# controller.net
KiCad netlist of a schematic drawn in Altium Designer
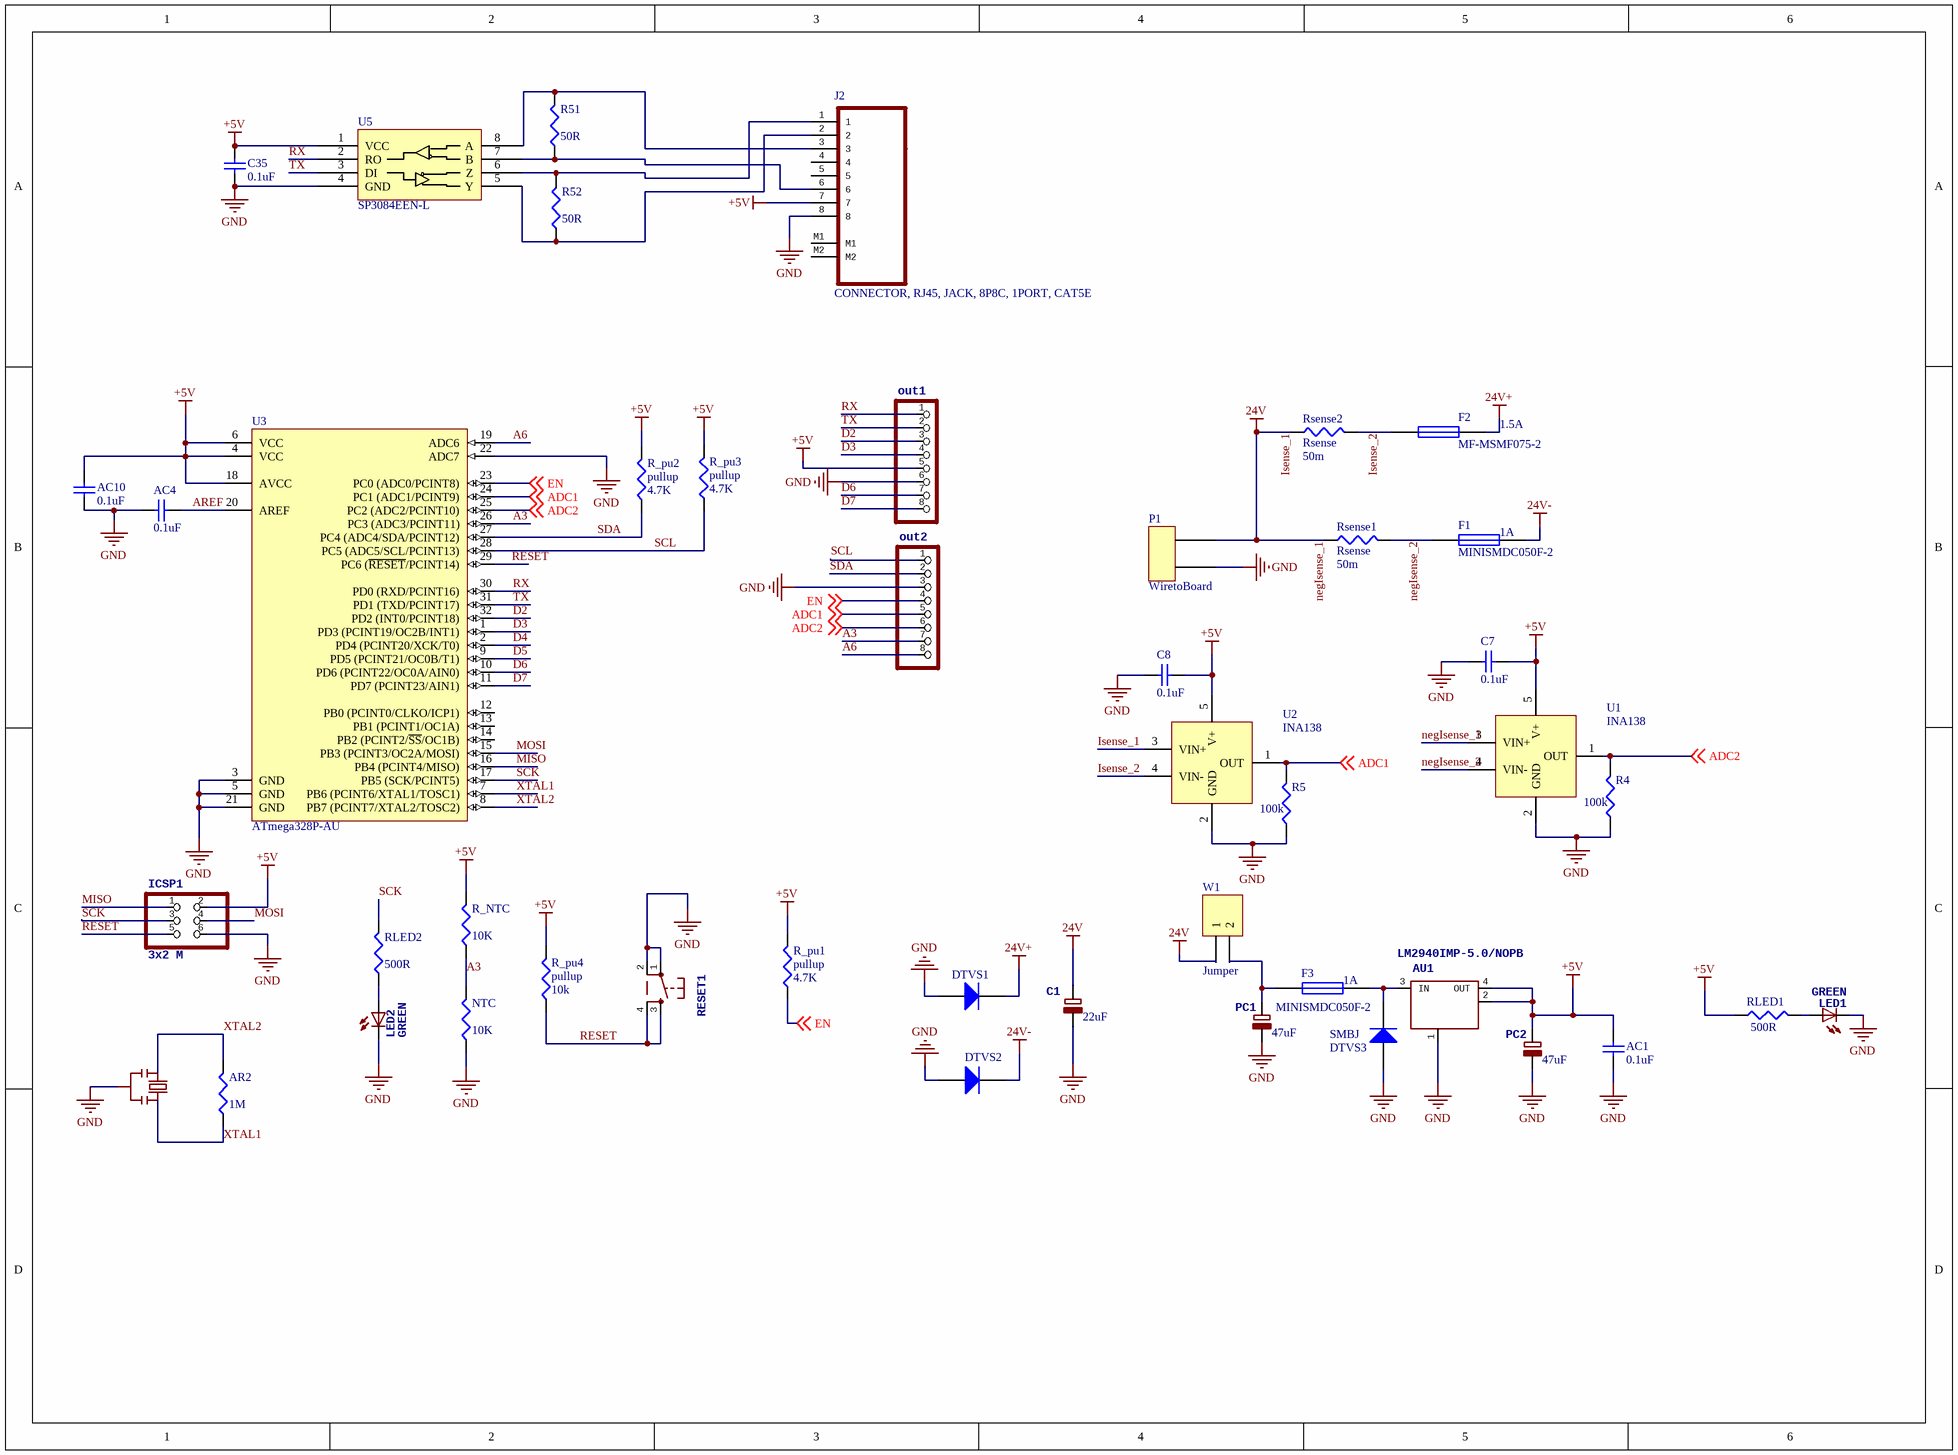
[diagram p0: controller.SchDoc]

(export (version "E")
  (design (tool "Eeschema 10.0.6"))
  (components
    (comp (ref "AC1")
      (value "0.1uF")
      (footprint "1608[0603]")
      (description "Capacitor (Semiconductor SIM Model)")
      (fields
        (field (name "PARTNO") "CC0603KRX7R9BB104")
        (field (name "Comment") "100n")
        (field (name "PUBLISHER") "Altium Limited")
      )
      (libsource (lib "Miscellaneous Devices") (part "Cap Semi"))
    )
    (comp (ref "AC4")
      (value "0.1uF")
      (footprint "1608[0603]")
      (description "Capacitor (Semiconductor SIM Model)")
      (fields
        (field (name "PARTNO") "CC0603KRX7R9BB104")
        (field (name "Comment") "Cap Semi")
        (field (name "PUBLISHER") "Altium Limited")
      )
      (libsource (lib "Miscellaneous Devices") (part "Cap Semi"))
    )
    (comp (ref "AC10")
      (value "0.1uF")
      (footprint "1608[0603]")
      (description "Capacitor (Semiconductor SIM Model)")
      (fields
        (field (name "PARTNO") "CC0603KRX7R9BB104")
        (field (name "Comment") "Cap Semi")
        (field (name "PUBLISHER") "Altium Limited")
      )
      (libsource (lib "Miscellaneous Devices") (part "Cap Semi"))
    )
    (comp (ref "AR2")
      (value "1M")
      (footprint "J1-0603")
      (description "Resistor")
      (fields (field (name "PUBLISHER") "Altium Limited"))
      (libsource (lib "Miscellaneous Devices") (part "Res3"))
    )
    (comp (ref "AU1")
      (value "LM2940IMP-5.0/NOPB")
      (footprint "SOT223")
      (description "1469076")
      (libsource (lib "arduino_Uno_Rev3-02-TH") (part "MC33269ST*"))
    )
    (comp (ref "C1")
      (value "22uF")
      (footprint "PANASONIC_D")
      (fields (field (name "PARTNO") "EMZA500ADA220MF61G"))
      (libsource (lib "G2_LV") (part "CPOL-EUD"))
    )
    (comp (ref "C7")
      (value "0.1uF")
      (footprint "1608[0603]")
      (description "Capacitor (Semiconductor SIM Model)")
      (fields
        (field (name "PARTNO") "CC0603KRX7R9BB104")
        (field (name "Comment") "Cap Semi")
        (field (name "PUBLISHER") "Altium Limited")
      )
      (libsource (lib "Miscellaneous Devices") (part "Cap Semi"))
    )
    (comp (ref "C8")
      (value "0.1uF")
      (footprint "1608[0603]")
      (description "Capacitor (Semiconductor SIM Model)")
      (fields
        (field (name "PARTNO") "CC0603KRX7R9BB104")
        (field (name "Comment") "Cap Semi")
        (field (name "PUBLISHER") "Altium Limited")
      )
      (libsource (lib "Miscellaneous Devices") (part "Cap Semi"))
    )
    (comp (ref "C35")
      (value "0.1uF")
      (footprint "1608[0603]")
      (description "Capacitor (Semiconductor SIM Model)")
      (fields
        (field (name "PARTNO") "CC0603KRX7R9BB104")
        (field (name "Comment") "Cap Semi")
        (field (name "PUBLISHER") "Altium Limited")
      )
      (libsource (lib "Miscellaneous Devices") (part "Cap Semi"))
    )
    (comp (ref "DTVS1")
      (value "SMBJ24A-E3/52")
      (footprint "DO-214AA")
      (description "TVS")
      (fields (field (name "PUBLISHER") "Altium Limited"))
      (libsource (lib "G2_LV") (part "SMBJ"))
    )
    (comp (ref "DTVS2")
      (value "SMBJ")
      (footprint "DO-214AA")
      (description "TVS")
      (fields (field (name "PARTNO") "SMBJ24A-E3/52") (field (name "PUBLISHER") "Altium Limited"))
      (libsource (lib "G2_LV") (part "SMBJ"))
    )
    (comp (ref "DTVS3")
      (value "SMBJ")
      (footprint "DO-214AA")
      (description "TVS")
      (fields (field (name "PARTNO") "SMBJ24A-E3/52") (field (name "PUBLISHER") "Altium Limited"))
      (libsource (lib "G2_LV") (part "SMBJ"))
    )
    (comp (ref "F1")
      (value "MINISMDC050F-2")
      (footprint "MF-MSMF1")
      (description "Fuse")
      (fields (field (name "TRIPPING CURRENT") "1A") (field (name "PUBLISHER") "Altium Limited"))
      (libsource (lib "G2_LV") (part "Fuse 1"))
    )
    (comp (ref "F2")
      (value "MF-MSMF075-2")
      (footprint "MF-MSMF1")
      (description "Fuse")
      (fields
        (field (name "TRIPPING CURRENT") "1.5A")
        (field (name "PARTNO") "MF-MSMF075/24-2")
        (field (name "PUBLISHER") "Altium Limited")
      )
      (libsource (lib "G2_LV") (part "Fuse 1"))
    )
    (comp (ref "F3")
      (value "MINISMDC050F-2")
      (footprint "MF-MSMF1")
      (description "Fuse")
      (fields (field (name "TRIPPING CURRENT") "1A") (field (name "PUBLISHER") "Altium Limited"))
      (libsource (lib "G2_LV") (part "Fuse 1"))
    )
    (comp (ref "ICSP1")
      (value "3x2 M")
      (footprint "2X03")
      (fields (field (name "PARTNO") "M20-9980345"))
      (libsource (lib "SmartPrj") (part "PINHD-2X3"))
    )
    (comp (ref "J2")
      (value "CONNECTOR, RJ45, JACK, 8P8C, 1PORT, CAT5E")
      (footprint "MOLEX_85505-5113")
      (fields (field (name "MPN") "85505-5113"))
      (libsource (lib "G2_LV") (part "85505-5113"))
    )
    (comp (ref "LED1")
      (value "GREEN")
      (footprint "CHIP-LED0805")
      (fields (field (name "PARTNO") "KPT-2012SGC"))
      (libsource (lib "led") (part "LEDCHIP-LED0805"))
    )
    (comp (ref "LED2")
      (value "GREEN")
      (footprint "CHIP-LED0805")
      (fields (field (name "PARTNO") "KPT-2012SGC"))
      (libsource (lib "led") (part "LEDCHIP-LED0805"))
    )
    (comp (ref "NTC")
      (value "10K")
      (footprint "J1-0603")
      (description "Resistor")
      (fields (field (name "PARTNO") "NCP18XH103J03RB") (field (name "PUBLISHER") "Altium Limited"))
      (libsource (lib "Miscellaneous Devices") (part "Res3"))
    )
    (comp (ref "out1")
      (value "~")
      (footprint "1X08")
      (fields (field (name "PARTNO") "5-534237-4"))
      (libsource (lib "SmartPrj") (part "PINHD-1X8"))
    )
    (comp (ref "out2")
      (value "~")
      (footprint "1X08")
      (fields (field (name "PARTNO") "5-534237-4"))
      (libsource (lib "SmartPrj") (part "PINHD-1X8"))
    )
    (comp (ref "P1")
      (value "WiretoBoard")
      (footprint "MC000044")
      (fields (field (name "PARTNO") "64T3402"))
      (libsource (lib "PCB_Project") (part "WiretoBoard"))
    )
    (comp (ref "PC1")
      (value "47uF")
      (footprint "PANASONIC_D")
      (fields
        (field (name "PARTNO") "EEE1EA470WAP")
        (field (name "Comment") "<B>POLARIZED CAPACITOR</B>, European symbol")
      )
      (libsource (lib "G2_LV") (part "CPOL-EUD"))
    )
    (comp (ref "PC2")
      (value "47uF")
      (footprint "PANASONIC_D")
      (fields
        (field (name "PARTNO") "EEE1EA470WAP")
        (field (name "Comment") "<B>POLARIZED CAPACITOR</B>, European symbol")
      )
      (libsource (lib "G2_LV") (part "CPOL-EUD"))
    )
    (comp (ref "R4")
      (value "100k")
      (footprint "J1-0603")
      (description "Resistor")
      (fields (field (name "Comment") "Res3") (field (name "PUBLISHER") "Altium Limited"))
      (libsource (lib "Miscellaneous Devices") (part "Res3"))
    )
    (comp (ref "R5")
      (value "100k")
      (footprint "J1-0603")
      (description "Resistor")
      (fields (field (name "Comment") "Res3") (field (name "PUBLISHER") "Altium Limited"))
      (libsource (lib "Miscellaneous Devices") (part "Res3"))
    )
    (comp (ref "R51")
      (value "50R")
      (footprint "J1-0603")
      (description "Resistor")
      (fields (field (name "PUBLISHER") "Altium Limited"))
      (libsource (lib "Miscellaneous Devices") (part "Res3"))
    )
    (comp (ref "R52")
      (value "50R")
      (footprint "J1-0603")
      (description "Resistor")
      (fields (field (name "PUBLISHER") "Altium Limited"))
      (libsource (lib "Miscellaneous Devices") (part "Res3"))
    )
    (comp (ref "RESET1")
      (value "~")
      (footprint "B3S-1002")
      (fields (field (name "PARTNO") "B3S-1002"))
      (libsource (lib "arduino_Uno_Rev3-02-TH") (part "TS42"))
    )
    (comp (ref "RLED1")
      (value "500R")
      (footprint "J1-0603")
      (description "Resistor")
      (fields (field (name "PUBLISHER") "Altium Limited"))
      (libsource (lib "Miscellaneous Devices") (part "Res3"))
    )
    (comp (ref "RLED2")
      (value "500R")
      (footprint "J1-0603")
      (description "Resistor")
      (fields (field (name "PUBLISHER") "Altium Limited"))
      (libsource (lib "Miscellaneous Devices") (part "Res3"))
    )
    (comp (ref "Rsense1")
      (value "Rsense")
      (footprint "R6432")
      (description "CRF2512-FV-R001ELF")
      (fields
        (field (name "ALTIUM_VALUE") "50m")
        (field (name "PARTNO") "MCS3264R050FER")
        (field (name "PUBLISHER") "Altium Limited")
      )
      (libsource (lib "G2_LV") (part "Rsense"))
    )
    (comp (ref "Rsense2")
      (value "Rsense")
      (footprint "R6432")
      (description "CRF2512-FV-R001ELF")
      (fields
        (field (name "ALTIUM_VALUE") "50m")
        (field (name "PARTNO") "MCS3264R050FER")
        (field (name "PUBLISHER") "Altium Limited")
      )
      (libsource (lib "G2_LV") (part "Rsense"))
    )
    (comp (ref "R_NTC")
      (value "10K")
      (footprint "J1-0603")
      (description "Resistor")
      (fields (field (name "PUBLISHER") "Altium Limited"))
      (libsource (lib "Miscellaneous Devices") (part "Res3"))
    )
    (comp (ref "R_pu1")
      (value "pullup")
      (footprint "J1-0603")
      (description "Resistor")
      (fields (field (name "ALTIUM_VALUE") "4.7K") (field (name "PUBLISHER") "Altium Limited"))
      (libsource (lib "Miscellaneous Devices") (part "Res3"))
    )
    (comp (ref "R_pu2")
      (value "pullup")
      (footprint "J1-0603")
      (description "Resistor")
      (fields (field (name "ALTIUM_VALUE") "4.7K") (field (name "PUBLISHER") "Altium Limited"))
      (libsource (lib "Miscellaneous Devices") (part "Res3"))
    )
    (comp (ref "R_pu3")
      (value "pullup")
      (footprint "J1-0603")
      (description "Resistor")
      (fields (field (name "ALTIUM_VALUE") "4.7K") (field (name "PUBLISHER") "Altium Limited"))
      (libsource (lib "Miscellaneous Devices") (part "Res3"))
    )
    (comp (ref "R_pu4")
      (value "pullup")
      (footprint "J1-0603")
      (description "Resistor")
      (fields (field (name "ALTIUM_VALUE") "10k") (field (name "PUBLISHER") "Altium Limited"))
      (libsource (lib "Miscellaneous Devices") (part "Res3"))
    )
    (comp (ref "U1")
      (value "INA138")
      (footprint "SOT-23")
      (fields (field (name "PARTNO") "INA138NA/250"))
      (libsource (lib "PCB_Project") (part "INA138"))
    )
    (comp (ref "U2")
      (value "INA138")
      (footprint "SOT-23")
      (fields (field (name "PARTNO") "INA138NA/250"))
      (libsource (lib "PCB_Project") (part "INA138"))
    )
    (comp (ref "U3")
      (value "ATmega328P-AU")
      (footprint "32A_N")
      (libsource (lib "Atmel Microcontroller megaAVR") (part "ATmega328P-AU"))
    )
    (comp (ref "U5")
      (value "SP3084EEN-L")
      (footprint "SOICN8")
      (libsource (lib "G2_LV") (part "SP3084EEN-L"))
    )
    (comp (ref "W1")
      (value "Jumper")
      (footprint "HDR1X2")
      (description "Header, 2-Pin")
      (fields (field (name "PUBLISHER") "Altium Limited"))
      (libsource (lib "Miscellaneous Connectors") (part "Header 2"))
    )
    (comp (ref "Y1")
      (value "~")
      (footprint "RESONATOR")
      (fields (field (name "PARTNO") "CSTCE16M0V53-R0"))
      (libsource (lib "SmartPrj") (part "RESONATORMU"))
    )
  )
  (nets
    (net (code "1") (name "+5V") (class "Default")
      (node (ref "AC1") (pin "2") (pinfunction "2_2") (pintype "passive"))
      (node (ref "AC10") (pin "2") (pinfunction "2_2") (pintype "passive"))
      (node (ref "AU1") (pin "2") (pinfunction "OUT_2") (pintype "passive"))
      (node (ref "AU1") (pin "4") (pinfunction "OUT_4") (pintype "passive"))
      (node (ref "C35") (pin "2") (pinfunction "2_2") (pintype "passive"))
      (node (ref "C7") (pin "2") (pinfunction "2_2") (pintype "passive"))
      (node (ref "C8") (pin "2") (pinfunction "2_2") (pintype "passive"))
      (node (ref "ICSP1") (pin "2") (pinfunction "2_2") (pintype "passive"))
      (node (ref "J2") (pin "7") (pinfunction "7_7") (pintype "passive"))
      (node (ref "PC2") (pin "1") (pinfunction "1_1") (pintype "passive"))
      (node (ref "RLED1") (pin "1") (pinfunction "1_1") (pintype "passive"))
      (node (ref "R_NTC") (pin "2") (pinfunction "2_2") (pintype "passive"))
      (node (ref "R_pu1") (pin "2") (pinfunction "2_2") (pintype "passive"))
      (node (ref "R_pu2") (pin "2") (pinfunction "2_2") (pintype "passive"))
      (node (ref "R_pu3") (pin "2") (pinfunction "2_2") (pintype "passive"))
      (node (ref "R_pu4") (pin "2") (pinfunction "2_2") (pintype "passive"))
      (node (ref "U1") (pin "5") (pinfunction "V+_5") (pintype "passive"))
      (node (ref "U2") (pin "5") (pinfunction "V+_5") (pintype "passive"))
      (node (ref "U3") (pin "18") (pinfunction "AVCC_18") (pintype "power_in"))
      (node (ref "U3") (pin "4") (pinfunction "VCC_4") (pintype "power_in"))
      (node (ref "U3") (pin "6") (pinfunction "VCC_6") (pintype "power_in"))
      (node (ref "U5") (pin "1") (pinfunction "VCC_1") (pintype "passive"))
      (node (ref "out1") (pin "5") (pinfunction "5_5") (pintype "passive"))
    )
    (net (code "2") (name "/A3") (class "Default")
      (node (ref "NTC") (pin "2") (pinfunction "2_2") (pintype "passive"))
      (node (ref "R_NTC") (pin "1") (pinfunction "1_1") (pintype "passive"))
      (node (ref "U3") (pin "26") (pinfunction "PC3_(ADC3/PCINT11)_26") (pintype "bidirectional"))
      (node (ref "out2") (pin "7") (pinfunction "7_7") (pintype "passive"))
    )
    (net (code "3") (name "/A6") (class "Default")
      (node (ref "U3") (pin "19") (pinfunction "ADC6_19") (pintype "input"))
      (node (ref "out2") (pin "8") (pinfunction "8_8") (pintype "passive"))
    )
    (net (code "4") (name "/AREF") (class "Default")
      (node (ref "AC4") (pin "2") (pinfunction "2_2") (pintype "passive"))
      (node (ref "U3") (pin "20") (pinfunction "AREF_20") (pintype "passive"))
    )
    (net (code "5") (name "/D2") (class "Default")
      (node (ref "U3") (pin "32") (pinfunction "PD2_(INT0/PCINT18)_32") (pintype "bidirectional"))
      (node (ref "out1") (pin "3") (pinfunction "3_3") (pintype "passive"))
    )
    (net (code "6") (name "/D3") (class "Default")
      (node (ref "U3") (pin "1") (pinfunction "PD3_(PCINT19/OC2B/INT1)_1") (pintype "bidirectional"))
      (node (ref "out1") (pin "4") (pinfunction "4_4") (pintype "passive"))
    )
    (net (code "7") (name "/D4") (class "Default")
      (node (ref "U3") (pin "2") (pinfunction "PD4_(PCINT20/XCK/T0)_2") (pintype "bidirectional"))
    )
    (net (code "8") (name "/D5") (class "Default")
      (node (ref "U3") (pin "9") (pinfunction "PD5_(PCINT21/OC0B/T1)_9") (pintype "bidirectional"))
    )
    (net (code "9") (name "/D6") (class "Default")
      (node (ref "U3") (pin "10") (pinfunction "PD6_(PCINT22/OC0A/AIN0)_10") (pintype "bidirectional"))
      (node (ref "out1") (pin "7") (pinfunction "7_7") (pintype "passive"))
    )
    (net (code "10") (name "/D7") (class "Default")
      (node (ref "U3") (pin "11") (pinfunction "PD7_(PCINT23/AIN1)_11") (pintype "bidirectional"))
      (node (ref "out1") (pin "8") (pinfunction "8_8") (pintype "passive"))
    )
    (net (code "11") (name "/Isense_2") (class "Default")
      (node (ref "F2") (pin "1") (pinfunction "1_1") (pintype "passive"))
      (node (ref "Rsense2") (pin "2") (pinfunction "2_2") (pintype "passive"))
      (node (ref "U2") (pin "4") (pinfunction "VIN-_4") (pintype "passive"))
    )
    (net (code "12") (name "/MISO") (class "Default")
      (node (ref "ICSP1") (pin "1") (pinfunction "1_1") (pintype "passive"))
      (node (ref "U3") (pin "16") (pinfunction "PB4_(PCINT4/MISO)_16") (pintype "bidirectional"))
    )
    (net (code "13") (name "/MOSI") (class "Default")
      (node (ref "ICSP1") (pin "4") (pinfunction "4_4") (pintype "passive"))
      (node (ref "U3") (pin "15") (pinfunction "PB3_(PCINT3/OC2A/MOSI)_15") (pintype "bidirectional"))
    )
    (net (code "14") (name "/RESET") (class "Default")
      (node (ref "ICSP1") (pin "5") (pinfunction "5_5") (pintype "passive"))
      (node (ref "RESET1") (pin "3") (pinfunction "3_3") (pintype "passive"))
      (node (ref "RESET1") (pin "4") (pinfunction "4_4") (pintype "passive"))
      (node (ref "R_pu4") (pin "1") (pinfunction "1_1") (pintype "passive"))
      (node (ref "U3") (pin "29") (pinfunction "PC6_(~{RESET}/PCINT14)_29") (pintype "bidirectional"))
    )
    (net (code "15") (name "/RX") (class "Default")
      (node (ref "U3") (pin "30") (pinfunction "PD0_(RXD/PCINT16)_30") (pintype "bidirectional"))
      (node (ref "U5") (pin "2") (pinfunction "RO_2") (pintype "passive"))
      (node (ref "out1") (pin "1") (pinfunction "1_1") (pintype "passive"))
    )
    (net (code "16") (name "/SCK") (class "Default")
      (node (ref "ICSP1") (pin "3") (pinfunction "3_3") (pintype "passive"))
      (node (ref "RLED2") (pin "2") (pinfunction "2_2") (pintype "passive"))
      (node (ref "U3") (pin "17") (pinfunction "PB5_(SCK/PCINT5)_17") (pintype "bidirectional"))
    )
    (net (code "17") (name "/SCL") (class "Default")
      (node (ref "R_pu3") (pin "1") (pinfunction "1_1") (pintype "passive"))
      (node (ref "U3") (pin "28") (pinfunction "PC5_(ADC5/SCL/PCINT13)_28") (pintype "bidirectional"))
      (node (ref "out2") (pin "1") (pinfunction "1_1") (pintype "passive"))
    )
    (net (code "18") (name "/SDA") (class "Default")
      (node (ref "R_pu2") (pin "1") (pinfunction "1_1") (pintype "passive"))
      (node (ref "U3") (pin "27") (pinfunction "PC4_(ADC4/SDA/PCINT12)_27") (pintype "bidirectional"))
      (node (ref "out2") (pin "2") (pinfunction "2_2") (pintype "passive"))
    )
    (net (code "19") (name "/TX") (class "Default")
      (node (ref "U3") (pin "31") (pinfunction "PD1_(TXD/PCINT17)_31") (pintype "bidirectional"))
      (node (ref "U5") (pin "3") (pinfunction "DI_3") (pintype "passive"))
      (node (ref "out1") (pin "2") (pinfunction "2_2") (pintype "passive"))
    )
    (net (code "20") (name "/XTAL1") (class "Default")
      (node (ref "AR2") (pin "1") (pinfunction "1_1") (pintype "passive"))
      (node (ref "U3") (pin "7") (pinfunction "PB6_(PCINT6/XTAL1/TOSC1)_7") (pintype "bidirectional"))
      (node (ref "Y1") (pin "3") (pinfunction "3_3") (pintype "passive"))
    )
    (net (code "21") (name "/XTAL2") (class "Default")
      (node (ref "AR2") (pin "2") (pinfunction "2_2") (pintype "passive"))
      (node (ref "U3") (pin "8") (pinfunction "PB7_(PCINT7/XTAL2/TOSC2)_8") (pintype "bidirectional"))
      (node (ref "Y1") (pin "1") (pinfunction "1_1") (pintype "passive"))
    )
    (net (code "22") (name "/negIsense_2") (class "Default")
      (node (ref "F1") (pin "1") (pinfunction "1_1") (pintype "passive"))
      (node (ref "Rsense1") (pin "2") (pinfunction "2_2") (pintype "passive"))
      (node (ref "U1") (pin "4") (pinfunction "VIN-_4") (pintype "passive"))
    )
    (net (code "23") (name "24V") (class "Default")
      (node (ref "C1") (pin "1") (pinfunction "1_1") (pintype "passive"))
      (node (ref "P1") (pin "1") (pinfunction "1_1") (pintype "passive"))
      (node (ref "Rsense1") (pin "1") (pinfunction "1_1") (pintype "passive"))
      (node (ref "Rsense2") (pin "1") (pinfunction "1_1") (pintype "passive"))
      (node (ref "U1") (pin "3") (pinfunction "VIN+_3") (pintype "passive"))
      (node (ref "U2") (pin "3") (pinfunction "VIN+_3") (pintype "passive"))
      (node (ref "W1") (pin "1") (pinfunction "1_1") (pintype "passive"))
    )
    (net (code "24") (name "24V+") (class "Default")
      (node (ref "DTVS1") (pin "1") (pinfunction "K_1") (pintype "passive"))
      (node (ref "F2") (pin "2") (pinfunction "2_2") (pintype "passive"))
    )
    (net (code "25") (name "24V-") (class "Default")
      (node (ref "DTVS2") (pin "1") (pinfunction "K_1") (pintype "passive"))
      (node (ref "F1") (pin "2") (pinfunction "2_2") (pintype "passive"))
    )
    (net (code "26") (name "ADC1") (class "Default")
      (node (ref "R5") (pin "2") (pinfunction "2_2") (pintype "passive"))
      (node (ref "U2") (pin "1") (pinfunction "OUT_1") (pintype "passive"))
      (node (ref "U3") (pin "24") (pinfunction "PC1_(ADC1/PCINT9)_24") (pintype "bidirectional"))
      (node (ref "out2") (pin "5") (pinfunction "5_5") (pintype "passive"))
    )
    (net (code "27") (name "ADC2") (class "Default")
      (node (ref "R4") (pin "2") (pinfunction "2_2") (pintype "passive"))
      (node (ref "U1") (pin "1") (pinfunction "OUT_1") (pintype "passive"))
      (node (ref "U3") (pin "25") (pinfunction "PC2_(ADC2/PCINT10)_25") (pintype "bidirectional"))
      (node (ref "out2") (pin "6") (pinfunction "6_6") (pintype "passive"))
    )
    (net (code "28") (name "EN") (class "Default")
      (node (ref "R_pu1") (pin "1") (pinfunction "1_1") (pintype "passive"))
      (node (ref "U3") (pin "23") (pinfunction "PC0_(ADC0/PCINT8)_23") (pintype "bidirectional"))
      (node (ref "out2") (pin "4") (pinfunction "4_4") (pintype "passive"))
    )
    (net (code "29") (name "GND") (class "Default")
      (node (ref "AC1") (pin "1") (pinfunction "1_1") (pintype "passive"))
      (node (ref "AC10") (pin "1") (pinfunction "1_1") (pintype "passive"))
      (node (ref "AC4") (pin "1") (pinfunction "1_1") (pintype "passive"))
      (node (ref "AU1") (pin "1") (pinfunction "GND/ADJ_1") (pintype "passive"))
      (node (ref "C1") (pin "2") (pinfunction "2_2") (pintype "passive"))
      (node (ref "C35") (pin "1") (pinfunction "1_1") (pintype "passive"))
      (node (ref "C7") (pin "1") (pinfunction "1_1") (pintype "passive"))
      (node (ref "C8") (pin "1") (pinfunction "1_1") (pintype "passive"))
      (node (ref "DTVS1") (pin "2") (pinfunction "A_2") (pintype "passive"))
      (node (ref "DTVS2") (pin "2") (pinfunction "A_2") (pintype "passive"))
      (node (ref "DTVS3") (pin "2") (pinfunction "A_2") (pintype "passive"))
      (node (ref "ICSP1") (pin "6") (pinfunction "6_6") (pintype "passive"))
      (node (ref "J2") (pin "8") (pinfunction "8_8") (pintype "passive"))
      (node (ref "LED1") (pin "C") (pinfunction "C_C") (pintype "passive"))
      (node (ref "LED2") (pin "C") (pinfunction "C_C") (pintype "passive"))
      (node (ref "NTC") (pin "1") (pinfunction "1_1") (pintype "passive"))
      (node (ref "P1") (pin "2") (pinfunction "2_2") (pintype "passive"))
      (node (ref "PC1") (pin "2") (pinfunction "2_2") (pintype "passive"))
      (node (ref "PC2") (pin "2") (pinfunction "2_2") (pintype "passive"))
      (node (ref "R4") (pin "1") (pinfunction "1_1") (pintype "passive"))
      (node (ref "R5") (pin "1") (pinfunction "1_1") (pintype "passive"))
      (node (ref "RESET1") (pin "1") (pinfunction "1_1") (pintype "passive"))
      (node (ref "RESET1") (pin "2") (pinfunction "2_2") (pintype "passive"))
      (node (ref "U1") (pin "2") (pinfunction "GND_2") (pintype "passive"))
      (node (ref "U2") (pin "2") (pinfunction "GND_2") (pintype "passive"))
      (node (ref "U3") (pin "21") (pinfunction "GND_21") (pintype "power_in"))
      (node (ref "U3") (pin "22") (pinfunction "ADC7_22") (pintype "input"))
      (node (ref "U3") (pin "3") (pinfunction "GND_3") (pintype "power_in"))
      (node (ref "U3") (pin "5") (pinfunction "GND_5") (pintype "power_in"))
      (node (ref "U5") (pin "4") (pinfunction "GND_4") (pintype "passive"))
      (node (ref "Y1") (pin "2") (pinfunction "2_2") (pintype "passive"))
      (node (ref "out1") (pin "6") (pinfunction "6_6") (pintype "passive"))
      (node (ref "out2") (pin "3") (pinfunction "3_3") (pintype "passive"))
    )
    (net (code "30") (name "Net-(AU1-IN)") (class "Default")
      (node (ref "AU1") (pin "3") (pinfunction "IN_3") (pintype "passive"))
      (node (ref "DTVS3") (pin "1") (pinfunction "K_1") (pintype "passive"))
      (node (ref "F3") (pin "2") (pinfunction "2_2") (pintype "passive"))
    )
    (net (code "31") (name "Net-(F3-Pad1)") (class "Default")
      (node (ref "F3") (pin "1") (pinfunction "1_1") (pintype "passive"))
      (node (ref "PC1") (pin "1") (pinfunction "1_1") (pintype "passive"))
      (node (ref "W1") (pin "2") (pinfunction "2_2") (pintype "passive"))
    )
    (net (code "32") (name "Net-(LED1-PadA)") (class "Default")
      (node (ref "LED1") (pin "A") (pinfunction "A_A") (pintype "passive"))
      (node (ref "RLED1") (pin "2") (pinfunction "2_2") (pintype "passive"))
    )
    (net (code "33") (name "Net-(LED2-PadA)") (class "Default")
      (node (ref "LED2") (pin "A") (pinfunction "A_A") (pintype "passive"))
      (node (ref "RLED2") (pin "1") (pinfunction "1_1") (pintype "passive"))
    )
    (net (code "34") (name "Net-(U5-A)") (class "Default")
      (node (ref "J2") (pin "3") (pinfunction "3_3") (pintype "passive"))
      (node (ref "R51") (pin "2") (pinfunction "2_2") (pintype "passive"))
      (node (ref "U5") (pin "8") (pinfunction "A_8") (pintype "passive"))
    )
    (net (code "35") (name "Net-(U5-B)") (class "Default")
      (node (ref "J2") (pin "6") (pinfunction "6_6") (pintype "passive"))
      (node (ref "R51") (pin "1") (pinfunction "1_1") (pintype "passive"))
      (node (ref "U5") (pin "7") (pinfunction "B_7") (pintype "passive"))
    )
    (net (code "36") (name "Net-(U5-Y)") (class "Default")
      (node (ref "J2") (pin "2") (pinfunction "2_2") (pintype "passive"))
      (node (ref "R52") (pin "1") (pinfunction "1_1") (pintype "passive"))
      (node (ref "U5") (pin "5") (pinfunction "Y_5") (pintype "passive"))
    )
    (net (code "37") (name "Net-(U5-Z)") (class "Default")
      (node (ref "J2") (pin "1") (pinfunction "1_1") (pintype "passive"))
      (node (ref "R52") (pin "2") (pinfunction "2_2") (pintype "passive"))
      (node (ref "U5") (pin "6") (pinfunction "Z_6") (pintype "passive"))
    )
    (net (code "38") (name "unconnected-(J2-Pad4)") (class "Default")
      (node (ref "J2") (pin "4") (pinfunction "4_4") (pintype "passive"))
    )
    (net (code "39") (name "unconnected-(J2-Pad5)") (class "Default")
      (node (ref "J2") (pin "5") (pinfunction "5_5") (pintype "passive"))
    )
    (net (code "40") (name "unconnected-(J2-PadM1)") (class "Default")
      (node (ref "J2") (pin "M1") (pinfunction "M1_M1") (pintype "passive"))
    )
    (net (code "41") (name "unconnected-(J2-PadM2)") (class "Default")
      (node (ref "J2") (pin "M2") (pinfunction "M2_M2") (pintype "passive"))
    )
    (net (code "42") (name "unconnected-(U3-PB0_(PCINT0{slash}CLKO{slash}ICP1)-Pad12)") (class "Default")
      (node (ref "U3") (pin "12") (pinfunction "PB0_(PCINT0/CLKO/ICP1)_12") (pintype "bidirectional"))
    )
    (net (code "43") (name "unconnected-(U3-PB1_(PCINT1{slash}OC1A)-Pad13)") (class "Default")
      (node (ref "U3") (pin "13") (pinfunction "PB1_(PCINT1/OC1A)_13") (pintype "bidirectional"))
    )
    (net (code "44") (name "unconnected-(U3-PB2_(PCINT2{slash}~{SS}{slash}OC1B)-Pad14)") (class "Default")
      (node (ref "U3") (pin "14") (pinfunction "PB2_(PCINT2/~{SS}/OC1B)_14") (pintype "bidirectional"))
    )
  )
)
